# LVDS_Port.net
KiCad netlist of a schematic drawn in Altium Designer
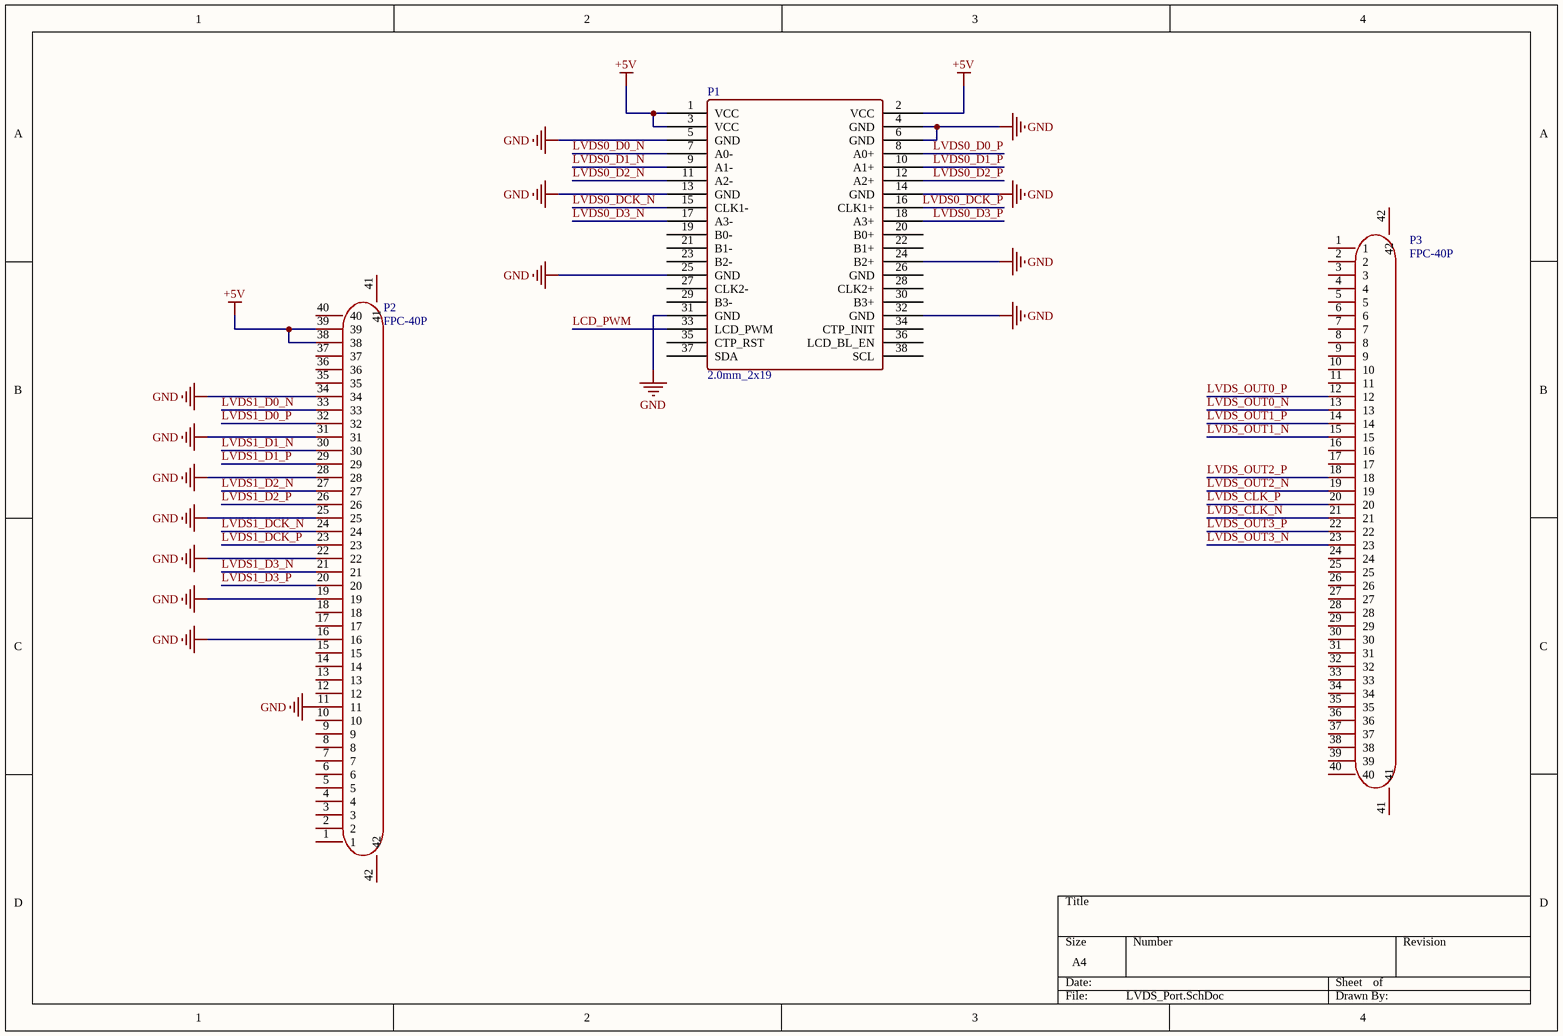
[diagram p0: LVDS_Port.SchDoc]

(export (version "E")
  (design (tool "Eeschema 10.0.6"))
  (components
    (comp (ref "P1")
      (value "2.0mm_2x19")
      (footprint "2.0mm_2x19")
      (libsource (lib "LVDS_Library") (part "2.0mm_2x19"))
    )
    (comp (ref "P2")
      (value "FPC-40P")
      (footprint "FPC-40P")
      (description "下接上翻盖")
      (libsource (lib "LVDS_Library") (part "FPC-40P"))
    )
    (comp (ref "P3")
      (value "FPC-40P")
      (footprint "FPC-40P")
      (description "下接上翻盖")
      (libsource (lib "LVDS_Library") (part "FPC-40P"))
    )
  )
  (nets
    (net (code "1") (name "+5V") (class "Default")
      (node (ref "P1") (pin "1") (pinfunction "VCC_1") (pintype "passive"))
      (node (ref "P1") (pin "2") (pinfunction "VCC_2") (pintype "passive"))
      (node (ref "P1") (pin "3") (pinfunction "VCC_3") (pintype "passive"))
      (node (ref "P2") (pin "38") (pinfunction "38_38") (pintype "passive"))
      (node (ref "P2") (pin "39") (pinfunction "39_39") (pintype "passive"))
    )
    (net (code "2") (name "/LCD_PWM") (class "Default")
      (node (ref "P1") (pin "33") (pinfunction "LCD_PWM_33") (pintype "passive"))
    )
    (net (code "3") (name "/LVDS0_D0_N") (class "Default")
      (node (ref "P1") (pin "7") (pinfunction "A0-_7") (pintype "passive"))
    )
    (net (code "4") (name "/LVDS0_D0_P") (class "Default")
      (node (ref "P1") (pin "8") (pinfunction "A0+_8") (pintype "passive"))
    )
    (net (code "5") (name "/LVDS0_D1_N") (class "Default")
      (node (ref "P1") (pin "9") (pinfunction "A1-_9") (pintype "passive"))
    )
    (net (code "6") (name "/LVDS0_D1_P") (class "Default")
      (node (ref "P1") (pin "10") (pinfunction "A1+_10") (pintype "passive"))
    )
    (net (code "7") (name "/LVDS0_D2_N") (class "Default")
      (node (ref "P1") (pin "11") (pinfunction "A2-_11") (pintype "passive"))
    )
    (net (code "8") (name "/LVDS0_D2_P") (class "Default")
      (node (ref "P1") (pin "12") (pinfunction "A2+_12") (pintype "passive"))
    )
    (net (code "9") (name "/LVDS0_D3_N") (class "Default")
      (node (ref "P1") (pin "17") (pinfunction "A3-_17") (pintype "passive"))
    )
    (net (code "10") (name "/LVDS0_D3_P") (class "Default")
      (node (ref "P1") (pin "18") (pinfunction "A3+_18") (pintype "passive"))
    )
    (net (code "11") (name "/LVDS0_DCK_N") (class "Default")
      (node (ref "P1") (pin "15") (pinfunction "CLK1-_15") (pintype "passive"))
    )
    (net (code "12") (name "/LVDS0_DCK_P") (class "Default")
      (node (ref "P1") (pin "16") (pinfunction "CLK1+_16") (pintype "passive"))
    )
    (net (code "13") (name "/LVDS1_D0_N") (class "Default")
      (node (ref "P2") (pin "33") (pinfunction "33_33") (pintype "passive"))
    )
    (net (code "14") (name "/LVDS1_D0_P") (class "Default")
      (node (ref "P2") (pin "32") (pinfunction "32_32") (pintype "passive"))
    )
    (net (code "15") (name "/LVDS1_D1_N") (class "Default")
      (node (ref "P2") (pin "30") (pinfunction "30_30") (pintype "passive"))
    )
    (net (code "16") (name "/LVDS1_D1_P") (class "Default")
      (node (ref "P2") (pin "29") (pinfunction "29_29") (pintype "passive"))
    )
    (net (code "17") (name "/LVDS1_D2_N") (class "Default")
      (node (ref "P2") (pin "27") (pinfunction "27_27") (pintype "passive"))
    )
    (net (code "18") (name "/LVDS1_D2_P") (class "Default")
      (node (ref "P2") (pin "26") (pinfunction "26_26") (pintype "passive"))
    )
    (net (code "19") (name "/LVDS1_D3_N") (class "Default")
      (node (ref "P2") (pin "21") (pinfunction "21_21") (pintype "passive"))
    )
    (net (code "20") (name "/LVDS1_D3_P") (class "Default")
      (node (ref "P2") (pin "20") (pinfunction "20_20") (pintype "passive"))
    )
    (net (code "21") (name "/LVDS1_DCK_N") (class "Default")
      (node (ref "P2") (pin "24") (pinfunction "24_24") (pintype "passive"))
    )
    (net (code "22") (name "/LVDS1_DCK_P") (class "Default")
      (node (ref "P2") (pin "23") (pinfunction "23_23") (pintype "passive"))
    )
    (net (code "23") (name "/LVDS_CLK_N") (class "Default")
      (node (ref "P3") (pin "21") (pinfunction "21_21") (pintype "passive"))
    )
    (net (code "24") (name "/LVDS_CLK_P") (class "Default")
      (node (ref "P3") (pin "20") (pinfunction "20_20") (pintype "passive"))
    )
    (net (code "25") (name "/LVDS_OUT0_N") (class "Default")
      (node (ref "P3") (pin "13") (pinfunction "13_13") (pintype "passive"))
    )
    (net (code "26") (name "/LVDS_OUT0_P") (class "Default")
      (node (ref "P3") (pin "12") (pinfunction "12_12") (pintype "passive"))
    )
    (net (code "27") (name "/LVDS_OUT1_N") (class "Default")
      (node (ref "P3") (pin "15") (pinfunction "15_15") (pintype "passive"))
    )
    (net (code "28") (name "/LVDS_OUT1_P") (class "Default")
      (node (ref "P3") (pin "14") (pinfunction "14_14") (pintype "passive"))
    )
    (net (code "29") (name "/LVDS_OUT2_N") (class "Default")
      (node (ref "P3") (pin "19") (pinfunction "19_19") (pintype "passive"))
    )
    (net (code "30") (name "/LVDS_OUT2_P") (class "Default")
      (node (ref "P3") (pin "18") (pinfunction "18_18") (pintype "passive"))
    )
    (net (code "31") (name "/LVDS_OUT3_N") (class "Default")
      (node (ref "P3") (pin "23") (pinfunction "23_23") (pintype "passive"))
    )
    (net (code "32") (name "/LVDS_OUT3_P") (class "Default")
      (node (ref "P3") (pin "22") (pinfunction "22_22") (pintype "passive"))
    )
    (net (code "33") (name "GND") (class "Default")
      (node (ref "P1") (pin "13") (pinfunction "GND_13") (pintype "passive"))
      (node (ref "P1") (pin "14") (pinfunction "GND_14") (pintype "passive"))
      (node (ref "P1") (pin "24") (pinfunction "B2+_24") (pintype "passive"))
      (node (ref "P1") (pin "25") (pinfunction "GND_25") (pintype "passive"))
      (node (ref "P1") (pin "31") (pinfunction "GND_31") (pintype "passive"))
      (node (ref "P1") (pin "32") (pinfunction "GND_32") (pintype "passive"))
      (node (ref "P1") (pin "4") (pinfunction "GND_4") (pintype "passive"))
      (node (ref "P1") (pin "5") (pinfunction "GND_5") (pintype "passive"))
      (node (ref "P1") (pin "6") (pinfunction "GND_6") (pintype "passive"))
      (node (ref "P2") (pin "11") (pinfunction "11_11") (pintype "passive"))
      (node (ref "P2") (pin "16") (pinfunction "16_16") (pintype "passive"))
      (node (ref "P2") (pin "19") (pinfunction "19_19") (pintype "passive"))
      (node (ref "P2") (pin "22") (pinfunction "22_22") (pintype "passive"))
      (node (ref "P2") (pin "25") (pinfunction "25_25") (pintype "passive"))
      (node (ref "P2") (pin "28") (pinfunction "28_28") (pintype "passive"))
      (node (ref "P2") (pin "31") (pinfunction "31_31") (pintype "passive"))
      (node (ref "P2") (pin "34") (pinfunction "34_34") (pintype "passive"))
    )
    (net (code "34") (name "unconnected-(P1-B0+-Pad20)") (class "Default")
      (node (ref "P1") (pin "20") (pinfunction "B0+_20") (pintype "passive"))
    )
    (net (code "35") (name "unconnected-(P1-B0--Pad19)") (class "Default")
      (node (ref "P1") (pin "19") (pinfunction "B0-_19") (pintype "passive"))
    )
    (net (code "36") (name "unconnected-(P1-B1+-Pad22)") (class "Default")
      (node (ref "P1") (pin "22") (pinfunction "B1+_22") (pintype "passive"))
    )
    (net (code "37") (name "unconnected-(P1-B1--Pad21)") (class "Default")
      (node (ref "P1") (pin "21") (pinfunction "B1-_21") (pintype "passive"))
    )
    (net (code "38") (name "unconnected-(P1-B2--Pad23)") (class "Default")
      (node (ref "P1") (pin "23") (pinfunction "B2-_23") (pintype "passive"))
    )
    (net (code "39") (name "unconnected-(P1-B3+-Pad30)") (class "Default")
      (node (ref "P1") (pin "30") (pinfunction "B3+_30") (pintype "passive"))
    )
    (net (code "40") (name "unconnected-(P1-B3--Pad29)") (class "Default")
      (node (ref "P1") (pin "29") (pinfunction "B3-_29") (pintype "passive"))
    )
    (net (code "41") (name "unconnected-(P1-CLK2+-Pad28)") (class "Default")
      (node (ref "P1") (pin "28") (pinfunction "CLK2+_28") (pintype "passive"))
    )
    (net (code "42") (name "unconnected-(P1-CLK2--Pad27)") (class "Default")
      (node (ref "P1") (pin "27") (pinfunction "CLK2-_27") (pintype "passive"))
    )
    (net (code "43") (name "unconnected-(P1-CTP_INIT-Pad34)") (class "Default")
      (node (ref "P1") (pin "34") (pinfunction "CTP_INIT_34") (pintype "passive"))
    )
    (net (code "44") (name "unconnected-(P1-CTP_RST-Pad35)") (class "Default")
      (node (ref "P1") (pin "35") (pinfunction "CTP_RST_35") (pintype "passive"))
    )
    (net (code "45") (name "unconnected-(P1-GND-Pad26)") (class "Default")
      (node (ref "P1") (pin "26") (pinfunction "GND_26") (pintype "passive"))
    )
    (net (code "46") (name "unconnected-(P1-LCD_BL_EN-Pad36)") (class "Default")
      (node (ref "P1") (pin "36") (pinfunction "LCD_BL_EN_36") (pintype "passive"))
    )
    (net (code "47") (name "unconnected-(P1-SCL-Pad38)") (class "Default")
      (node (ref "P1") (pin "38") (pinfunction "SCL_38") (pintype "passive"))
    )
    (net (code "48") (name "unconnected-(P1-SDA-Pad37)") (class "Default")
      (node (ref "P1") (pin "37") (pinfunction "SDA_37") (pintype "passive"))
    )
    (net (code "49") (name "unconnected-(P2-Pad1)") (class "Default")
      (node (ref "P2") (pin "1") (pinfunction "1_1") (pintype "passive"))
    )
    (net (code "50") (name "unconnected-(P2-Pad2)") (class "Default")
      (node (ref "P2") (pin "2") (pinfunction "2_2") (pintype "passive"))
    )
    (net (code "51") (name "unconnected-(P2-Pad3)") (class "Default")
      (node (ref "P2") (pin "3") (pinfunction "3_3") (pintype "passive"))
    )
    (net (code "52") (name "unconnected-(P2-Pad4)") (class "Default")
      (node (ref "P2") (pin "4") (pinfunction "4_4") (pintype "passive"))
    )
    (net (code "53") (name "unconnected-(P2-Pad5)") (class "Default")
      (node (ref "P2") (pin "5") (pinfunction "5_5") (pintype "passive"))
    )
    (net (code "54") (name "unconnected-(P2-Pad6)") (class "Default")
      (node (ref "P2") (pin "6") (pinfunction "6_6") (pintype "passive"))
    )
    (net (code "55") (name "unconnected-(P2-Pad7)") (class "Default")
      (node (ref "P2") (pin "7") (pinfunction "7_7") (pintype "passive"))
    )
    (net (code "56") (name "unconnected-(P2-Pad8)") (class "Default")
      (node (ref "P2") (pin "8") (pinfunction "8_8") (pintype "passive"))
    )
    (net (code "57") (name "unconnected-(P2-Pad9)") (class "Default")
      (node (ref "P2") (pin "9") (pinfunction "9_9") (pintype "passive"))
    )
    (net (code "58") (name "unconnected-(P2-Pad10)") (class "Default")
      (node (ref "P2") (pin "10") (pinfunction "10_10") (pintype "passive"))
    )
    (net (code "59") (name "unconnected-(P2-Pad12)") (class "Default")
      (node (ref "P2") (pin "12") (pinfunction "12_12") (pintype "passive"))
    )
    (net (code "60") (name "unconnected-(P2-Pad13)") (class "Default")
      (node (ref "P2") (pin "13") (pinfunction "13_13") (pintype "passive"))
    )
    (net (code "61") (name "unconnected-(P2-Pad14)") (class "Default")
      (node (ref "P2") (pin "14") (pinfunction "14_14") (pintype "passive"))
    )
    (net (code "62") (name "unconnected-(P2-Pad15)") (class "Default")
      (node (ref "P2") (pin "15") (pinfunction "15_15") (pintype "passive"))
    )
    (net (code "63") (name "unconnected-(P2-Pad17)") (class "Default")
      (node (ref "P2") (pin "17") (pinfunction "17_17") (pintype "passive"))
    )
    (net (code "64") (name "unconnected-(P2-Pad18)") (class "Default")
      (node (ref "P2") (pin "18") (pinfunction "18_18") (pintype "passive"))
    )
    (net (code "65") (name "unconnected-(P2-Pad35)") (class "Default")
      (node (ref "P2") (pin "35") (pinfunction "35_35") (pintype "passive"))
    )
    (net (code "66") (name "unconnected-(P2-Pad36)") (class "Default")
      (node (ref "P2") (pin "36") (pinfunction "36_36") (pintype "passive"))
    )
    (net (code "67") (name "unconnected-(P2-Pad37)") (class "Default")
      (node (ref "P2") (pin "37") (pinfunction "37_37") (pintype "passive"))
    )
    (net (code "68") (name "unconnected-(P2-Pad40)") (class "Default")
      (node (ref "P2") (pin "40") (pinfunction "40_40") (pintype "passive"))
    )
    (net (code "69") (name "unconnected-(P2-Pad41)") (class "Default")
      (node (ref "P2") (pin "41") (pinfunction "41_41") (pintype "passive"))
    )
    (net (code "70") (name "unconnected-(P2-Pad42)") (class "Default")
      (node (ref "P2") (pin "42") (pinfunction "42_42") (pintype "passive"))
    )
    (net (code "71") (name "unconnected-(P3-Pad1)") (class "Default")
      (node (ref "P3") (pin "1") (pinfunction "1_1") (pintype "passive"))
    )
    (net (code "72") (name "unconnected-(P3-Pad2)") (class "Default")
      (node (ref "P3") (pin "2") (pinfunction "2_2") (pintype "passive"))
    )
    (net (code "73") (name "unconnected-(P3-Pad3)") (class "Default")
      (node (ref "P3") (pin "3") (pinfunction "3_3") (pintype "passive"))
    )
    (net (code "74") (name "unconnected-(P3-Pad4)") (class "Default")
      (node (ref "P3") (pin "4") (pinfunction "4_4") (pintype "passive"))
    )
    (net (code "75") (name "unconnected-(P3-Pad5)") (class "Default")
      (node (ref "P3") (pin "5") (pinfunction "5_5") (pintype "passive"))
    )
    (net (code "76") (name "unconnected-(P3-Pad6)") (class "Default")
      (node (ref "P3") (pin "6") (pinfunction "6_6") (pintype "passive"))
    )
    (net (code "77") (name "unconnected-(P3-Pad7)") (class "Default")
      (node (ref "P3") (pin "7") (pinfunction "7_7") (pintype "passive"))
    )
    (net (code "78") (name "unconnected-(P3-Pad8)") (class "Default")
      (node (ref "P3") (pin "8") (pinfunction "8_8") (pintype "passive"))
    )
    (net (code "79") (name "unconnected-(P3-Pad9)") (class "Default")
      (node (ref "P3") (pin "9") (pinfunction "9_9") (pintype "passive"))
    )
    (net (code "80") (name "unconnected-(P3-Pad10)") (class "Default")
      (node (ref "P3") (pin "10") (pinfunction "10_10") (pintype "passive"))
    )
    (net (code "81") (name "unconnected-(P3-Pad11)") (class "Default")
      (node (ref "P3") (pin "11") (pinfunction "11_11") (pintype "passive"))
    )
    (net (code "82") (name "unconnected-(P3-Pad16)") (class "Default")
      (node (ref "P3") (pin "16") (pinfunction "16_16") (pintype "passive"))
    )
    (net (code "83") (name "unconnected-(P3-Pad17)") (class "Default")
      (node (ref "P3") (pin "17") (pinfunction "17_17") (pintype "passive"))
    )
    (net (code "84") (name "unconnected-(P3-Pad24)") (class "Default")
      (node (ref "P3") (pin "24") (pinfunction "24_24") (pintype "passive"))
    )
    (net (code "85") (name "unconnected-(P3-Pad25)") (class "Default")
      (node (ref "P3") (pin "25") (pinfunction "25_25") (pintype "passive"))
    )
    (net (code "86") (name "unconnected-(P3-Pad26)") (class "Default")
      (node (ref "P3") (pin "26") (pinfunction "26_26") (pintype "passive"))
    )
    (net (code "87") (name "unconnected-(P3-Pad27)") (class "Default")
      (node (ref "P3") (pin "27") (pinfunction "27_27") (pintype "passive"))
    )
    (net (code "88") (name "unconnected-(P3-Pad28)") (class "Default")
      (node (ref "P3") (pin "28") (pinfunction "28_28") (pintype "passive"))
    )
    (net (code "89") (name "unconnected-(P3-Pad29)") (class "Default")
      (node (ref "P3") (pin "29") (pinfunction "29_29") (pintype "passive"))
    )
    (net (code "90") (name "unconnected-(P3-Pad30)") (class "Default")
      (node (ref "P3") (pin "30") (pinfunction "30_30") (pintype "passive"))
    )
    (net (code "91") (name "unconnected-(P3-Pad31)") (class "Default")
      (node (ref "P3") (pin "31") (pinfunction "31_31") (pintype "passive"))
    )
    (net (code "92") (name "unconnected-(P3-Pad32)") (class "Default")
      (node (ref "P3") (pin "32") (pinfunction "32_32") (pintype "passive"))
    )
    (net (code "93") (name "unconnected-(P3-Pad33)") (class "Default")
      (node (ref "P3") (pin "33") (pinfunction "33_33") (pintype "passive"))
    )
    (net (code "94") (name "unconnected-(P3-Pad34)") (class "Default")
      (node (ref "P3") (pin "34") (pinfunction "34_34") (pintype "passive"))
    )
    (net (code "95") (name "unconnected-(P3-Pad35)") (class "Default")
      (node (ref "P3") (pin "35") (pinfunction "35_35") (pintype "passive"))
    )
    (net (code "96") (name "unconnected-(P3-Pad36)") (class "Default")
      (node (ref "P3") (pin "36") (pinfunction "36_36") (pintype "passive"))
    )
    (net (code "97") (name "unconnected-(P3-Pad37)") (class "Default")
      (node (ref "P3") (pin "37") (pinfunction "37_37") (pintype "passive"))
    )
    (net (code "98") (name "unconnected-(P3-Pad38)") (class "Default")
      (node (ref "P3") (pin "38") (pinfunction "38_38") (pintype "passive"))
    )
    (net (code "99") (name "unconnected-(P3-Pad39)") (class "Default")
      (node (ref "P3") (pin "39") (pinfunction "39_39") (pintype "passive"))
    )
    (net (code "100") (name "unconnected-(P3-Pad40)") (class "Default")
      (node (ref "P3") (pin "40") (pinfunction "40_40") (pintype "passive"))
    )
    (net (code "101") (name "unconnected-(P3-Pad41)") (class "Default")
      (node (ref "P3") (pin "41") (pinfunction "41_41") (pintype "passive"))
    )
    (net (code "102") (name "unconnected-(P3-Pad42)") (class "Default")
      (node (ref "P3") (pin "42") (pinfunction "42_42") (pintype "passive"))
    )
  )
)
